# 3_ESP8266.net
KiCad netlist of a schematic drawn in Altium Designer
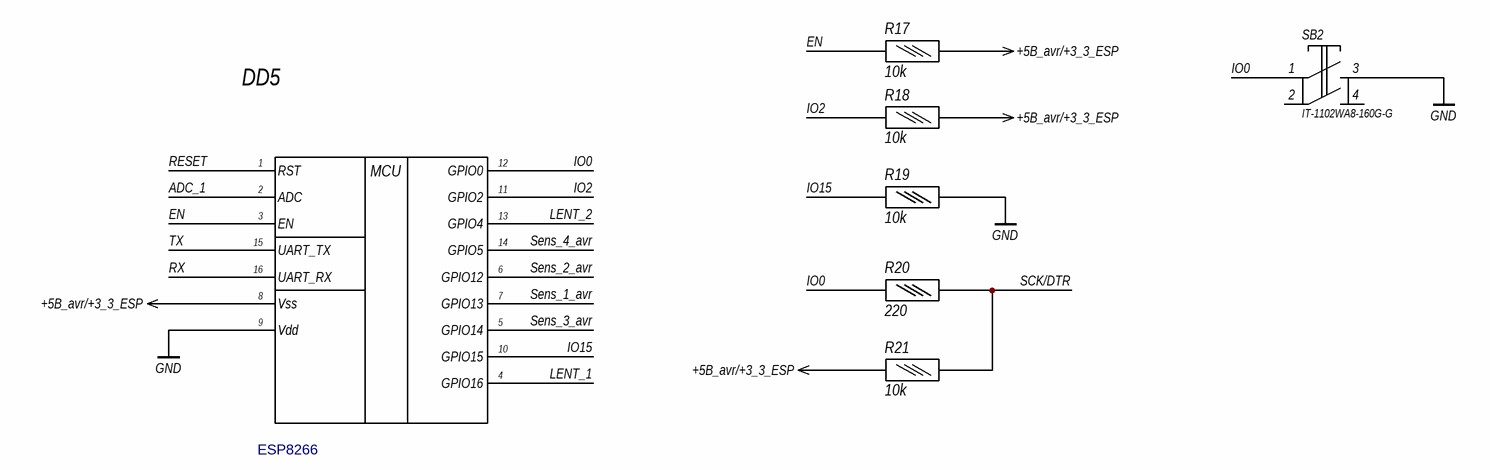
[diagram p0: Лист 3. ESP8266.SchDoc]

(export (version "E")
  (design (tool "Eeschema 10.0.6"))
  (components
    (comp (ref "DD5")
      (value "ESP8266")
      (footprint "ESP-12F")
      (description "MCU")
      (fields
        (field (name "PART NUMBER") "STM32F030F4P6")
        (field (name "MANUFACTURER") "ST Microelectronics")
      )
      (libsource (lib "Микросхемы") (part "ESP8266"))
    )
    (comp (ref "R17")
      (value "10k")
      (footprint "RESISTOR_0603_IPC782")
      (description "chip0603 10k 1%")
      (fields
        (field (name "VALUEMANUFACTURERPARTNUMBER") "chip0603 10k 1%, RC0603FR-0710KL, Yageo")
        (field (name "Comment") "RC0603FR-0710KL (0603 10k 1%)")
      )
      (libsource (lib "Резисторы") (part "RC0603FR-0710KL (0603 10k 1%)"))
    )
    (comp (ref "R18")
      (value "10k")
      (footprint "RESISTOR_0603_IPC782")
      (description "chip0603 10k 1%")
      (fields
        (field (name "VALUEMANUFACTURERPARTNUMBER") "chip0603 10k 1%, RC0603FR-0710KL, Yageo")
        (field (name "Comment") "RC0603FR-0710KL (0603 10k 1%)")
      )
      (libsource (lib "Резисторы") (part "RC0603FR-0710KL (0603 10k 1%)"))
    )
    (comp (ref "R19")
      (value "10k")
      (footprint "RESISTOR_0603_IPC782")
      (description "chip0603 10k 1%")
      (fields
        (field (name "VALUEMANUFACTURERPARTNUMBER") "chip0603 10k 1%, RC0603FR-0710KL, Yageo")
        (field (name "Comment") "RC0603FR-0710KL (0603 10k 1%)")
      )
      (libsource (lib "Резисторы") (part "RC0603FR-0710KL (0603 10k 1%)"))
    )
    (comp (ref "R20")
      (value "220")
      (footprint "RESISTOR_0603_IPC782")
      (description "chip0603 10k 1%")
      (fields
        (field (name "VALUEMANUFACTURERPARTNUMBER") "chip0603 10k 1%, RC0603FR-0710KL, Yageo")
        (field (name "Comment") "RC0603FR-0710KL (0603 10k 1%)")
      )
      (libsource (lib "Резисторы") (part "RC0603FR-0710KL (0603 10k 1%)"))
    )
    (comp (ref "R21")
      (value "10k")
      (footprint "RESISTOR_0603_IPC782")
      (description "chip0603 10k 1%")
      (fields
        (field (name "VALUEMANUFACTURERPARTNUMBER") "chip0603 10k 1%, RC0603FR-0710KL, Yageo")
        (field (name "Comment") "RC0603FR-0710KL (0603 10k 1%)")
      )
      (libsource (lib "Резисторы") (part "RC0603FR-0710KL (0603 10k 1%)"))
    )
    (comp (ref "SB2")
      (value "IT-1102WA8-160G-G")
      (footprint "TE FSM4JSMA")
      (fields (field (name "Comment") "button IT-1102WA8-160G-G"))
      (libsource (lib "Кнопки и переключатели") (part "button IT-1102WA8-160G-G"))
    )
  )
  (nets
    (net (code "1") (name "+5В_avr{slash}+3_3_ESP") (class "Default")
      (node (ref "DD5") (pin "8") (pinfunction "Vss_8") (pintype "power_in"))
      (node (ref "R17") (pin "2") (pinfunction "2_2") (pintype "passive"))
      (node (ref "R18") (pin "2") (pinfunction "2_2") (pintype "passive"))
      (node (ref "R21") (pin "1") (pinfunction "1_1") (pintype "passive"))
    )
    (net (code "2") (name "/ADC_1") (class "Default")
      (node (ref "DD5") (pin "2") (pinfunction "ADC_2") (pintype "passive"))
    )
    (net (code "3") (name "/EN") (class "Default")
      (node (ref "DD5") (pin "3") (pinfunction "EN_3") (pintype "passive"))
      (node (ref "R17") (pin "1") (pinfunction "1_1") (pintype "passive"))
    )
    (net (code "4") (name "/IO0") (class "Default")
      (node (ref "DD5") (pin "12") (pinfunction "GPIO0_12") (pintype "passive"))
      (node (ref "R20") (pin "1") (pinfunction "1_1") (pintype "passive"))
      (node (ref "SB2") (pin "1") (pinfunction "A_1") (pintype "passive"))
    )
    (net (code "5") (name "/IO2") (class "Default")
      (node (ref "DD5") (pin "11") (pinfunction "GPIO2_11") (pintype "passive"))
      (node (ref "R18") (pin "1") (pinfunction "1_1") (pintype "passive"))
    )
    (net (code "6") (name "/IO15") (class "Default")
      (node (ref "DD5") (pin "10") (pinfunction "GPIO15_10") (pintype "passive"))
      (node (ref "R19") (pin "1") (pinfunction "1_1") (pintype "passive"))
    )
    (net (code "7") (name "/LENT_1") (class "Default")
      (node (ref "DD5") (pin "4") (pinfunction "GPIO16_4") (pintype "passive"))
    )
    (net (code "8") (name "/LENT_2") (class "Default")
      (node (ref "DD5") (pin "13") (pinfunction "GPIO4_13") (pintype "passive"))
    )
    (net (code "9") (name "/RESET") (class "Default")
      (node (ref "DD5") (pin "1") (pinfunction "RST_1") (pintype "passive"))
    )
    (net (code "10") (name "/RX") (class "Default")
      (node (ref "DD5") (pin "16") (pinfunction "UART_RX_16") (pintype "passive"))
    )
    (net (code "11") (name "/SCK{slash}DTR") (class "Default")
      (node (ref "R20") (pin "2") (pinfunction "2_2") (pintype "passive"))
      (node (ref "R21") (pin "2") (pinfunction "2_2") (pintype "passive"))
    )
    (net (code "12") (name "/Sens_1_avr") (class "Default")
      (node (ref "DD5") (pin "7") (pinfunction "GPIO13_7") (pintype "passive"))
    )
    (net (code "13") (name "/Sens_2_avr") (class "Default")
      (node (ref "DD5") (pin "6") (pinfunction "GPIO12_6") (pintype "passive"))
    )
    (net (code "14") (name "/Sens_3_avr") (class "Default")
      (node (ref "DD5") (pin "5") (pinfunction "GPIO14_5") (pintype "passive"))
    )
    (net (code "15") (name "/Sens_4_avr") (class "Default")
      (node (ref "DD5") (pin "14") (pinfunction "GPIO5_14") (pintype "passive"))
    )
    (net (code "16") (name "/TX") (class "Default")
      (node (ref "DD5") (pin "15") (pinfunction "UART_TX_15") (pintype "passive"))
    )
    (net (code "17") (name "GND") (class "Default")
      (node (ref "DD5") (pin "9") (pinfunction "Vdd_9") (pintype "power_in"))
      (node (ref "R19") (pin "2") (pinfunction "2_2") (pintype "passive"))
      (node (ref "SB2") (pin "3") (pinfunction "C_3") (pintype "passive"))
    )
    (net (code "18") (name "unconnected-(SB2-A-Pad2)") (class "Default")
      (node (ref "SB2") (pin "2") (pinfunction "A_2") (pintype "passive"))
    )
    (net (code "19") (name "unconnected-(SB2-C-Pad4)") (class "Default")
      (node (ref "SB2") (pin "4") (pinfunction "C_4") (pintype "passive"))
    )
  )
)
